# circuit0.net
KiCad netlist of a schematic drawn in EAGLE
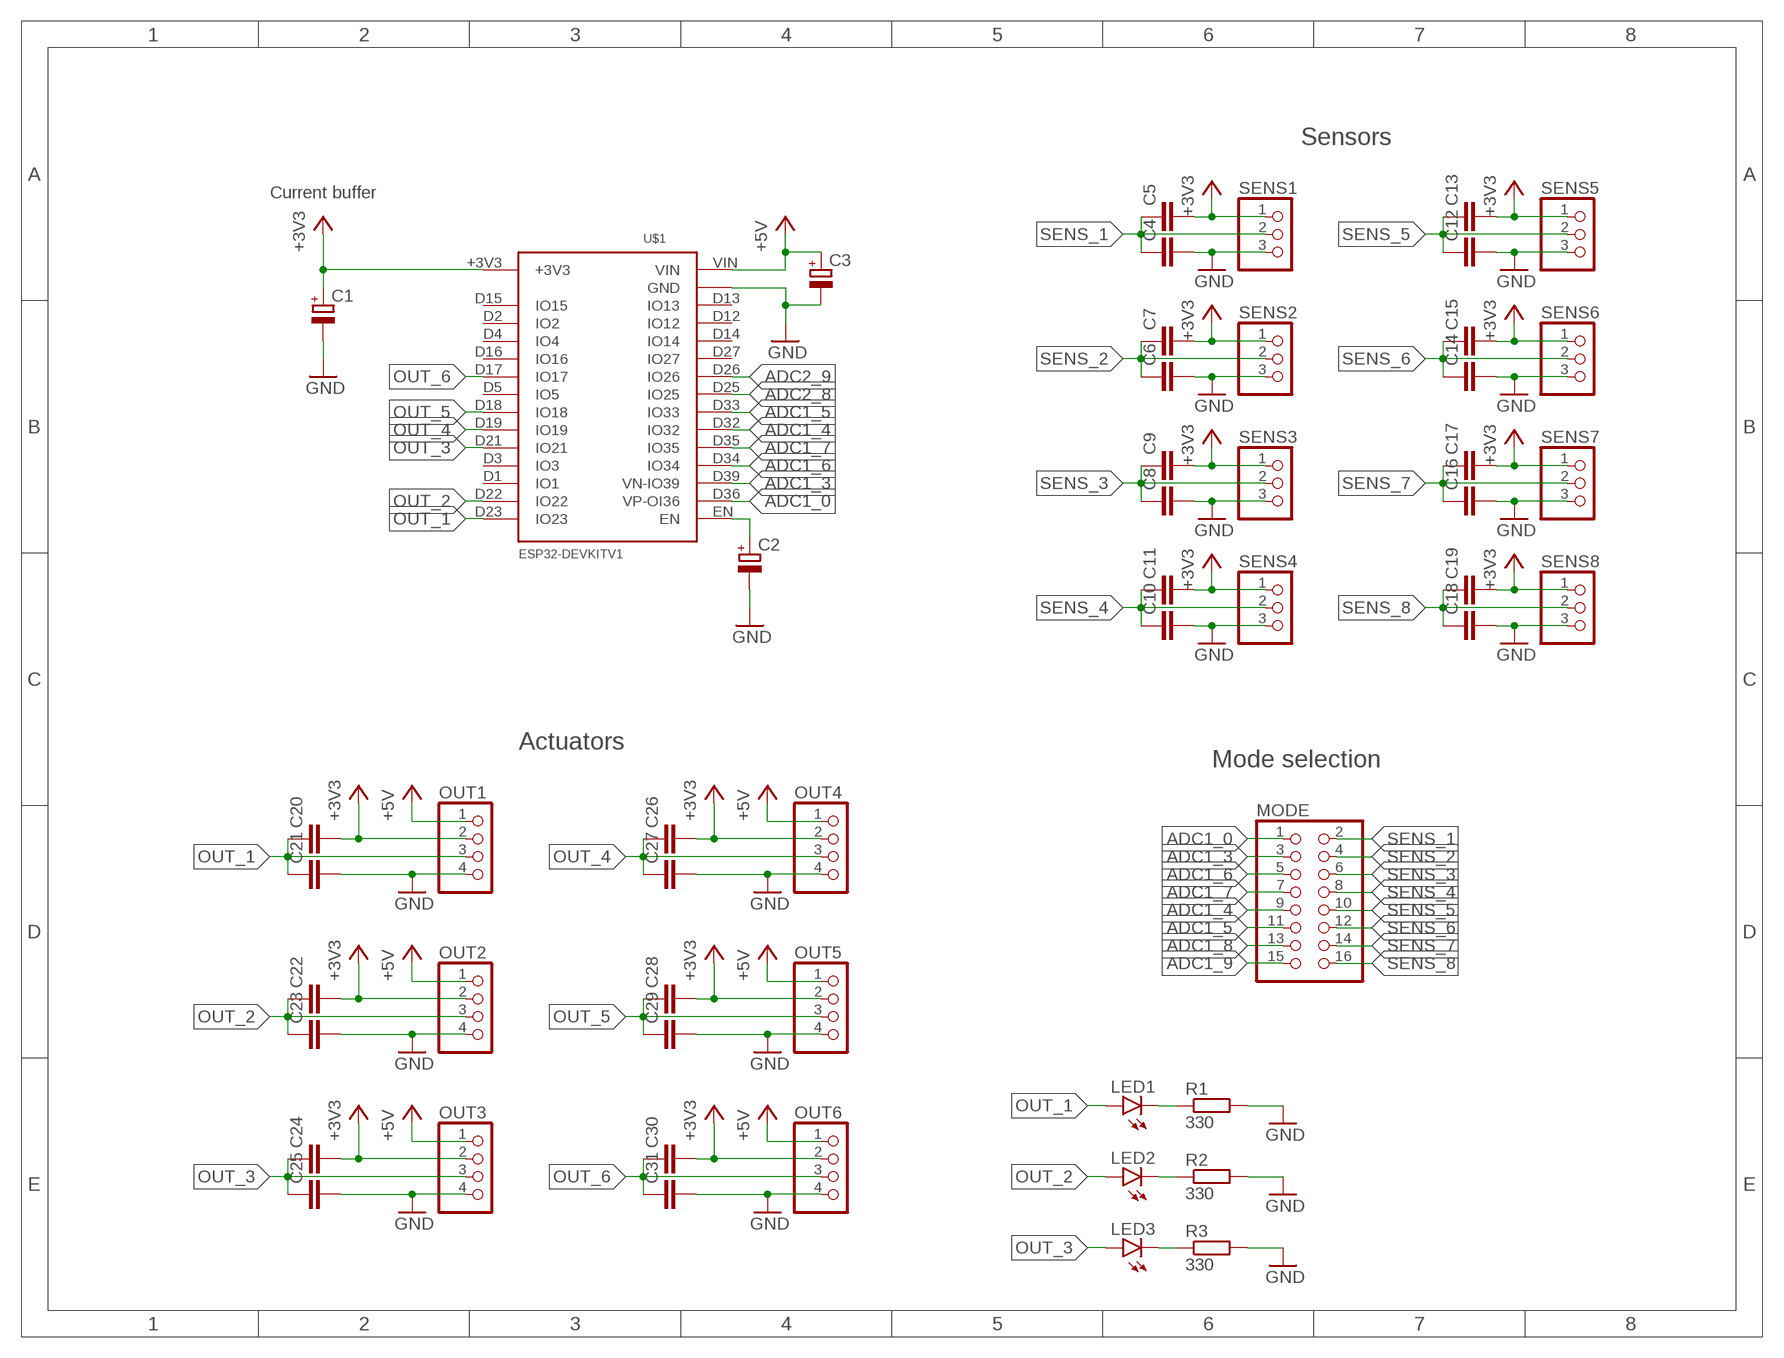
[diagram p0: schematic, sheet 1]

(export (version "E")
  (design (tool "Eeschema 10.0.6"))
  (components
    (comp (ref "C1")
      (value "CPOL-EUE3.5-8")
      (footprint "eagle-import:E3,5-8")
      (libsource (lib "eagle-import") (part "CPOL-EUE3.5-8"))
    )
    (comp (ref "C2")
      (value "CPOL-EUE3.5-8")
      (footprint "eagle-import:E3,5-8")
      (libsource (lib "eagle-import") (part "CPOL-EUE3.5-8"))
    )
    (comp (ref "C3")
      (value "CPOL-EUE3.5-8")
      (footprint "eagle-import:E3,5-8")
      (libsource (lib "eagle-import") (part "CPOL-EUE3.5-8"))
    )
    (comp (ref "C4")
      (value "C-EU025-030X050")
      (footprint "eagle-import:C025-030X050")
      (libsource (lib "eagle-import") (part "C-EU025-030X050"))
    )
    (comp (ref "C5")
      (value "C-EU025-030X050")
      (footprint "eagle-import:C025-030X050")
      (libsource (lib "eagle-import") (part "C-EU025-030X050"))
    )
    (comp (ref "C6")
      (value "C-EU025-030X050")
      (footprint "eagle-import:C025-030X050")
      (libsource (lib "eagle-import") (part "C-EU025-030X050"))
    )
    (comp (ref "C7")
      (value "C-EU025-030X050")
      (footprint "eagle-import:C025-030X050")
      (libsource (lib "eagle-import") (part "C-EU025-030X050"))
    )
    (comp (ref "C8")
      (value "C-EU025-030X050")
      (footprint "eagle-import:C025-030X050")
      (libsource (lib "eagle-import") (part "C-EU025-030X050"))
    )
    (comp (ref "C9")
      (value "C-EU025-030X050")
      (footprint "eagle-import:C025-030X050")
      (libsource (lib "eagle-import") (part "C-EU025-030X050"))
    )
    (comp (ref "C10")
      (value "C-EU025-030X050")
      (footprint "eagle-import:C025-030X050")
      (libsource (lib "eagle-import") (part "C-EU025-030X050"))
    )
    (comp (ref "C11")
      (value "C-EU025-030X050")
      (footprint "eagle-import:C025-030X050")
      (libsource (lib "eagle-import") (part "C-EU025-030X050"))
    )
    (comp (ref "C12")
      (value "C-EU025-030X050")
      (footprint "eagle-import:C025-030X050")
      (libsource (lib "eagle-import") (part "C-EU025-030X050"))
    )
    (comp (ref "C13")
      (value "C-EU025-030X050")
      (footprint "eagle-import:C025-030X050")
      (libsource (lib "eagle-import") (part "C-EU025-030X050"))
    )
    (comp (ref "C14")
      (value "C-EU025-030X050")
      (footprint "eagle-import:C025-030X050")
      (libsource (lib "eagle-import") (part "C-EU025-030X050"))
    )
    (comp (ref "C15")
      (value "C-EU025-030X050")
      (footprint "eagle-import:C025-030X050")
      (libsource (lib "eagle-import") (part "C-EU025-030X050"))
    )
    (comp (ref "C16")
      (value "C-EU025-030X050")
      (footprint "eagle-import:C025-030X050")
      (libsource (lib "eagle-import") (part "C-EU025-030X050"))
    )
    (comp (ref "C17")
      (value "C-EU025-030X050")
      (footprint "eagle-import:C025-030X050")
      (libsource (lib "eagle-import") (part "C-EU025-030X050"))
    )
    (comp (ref "C18")
      (value "C-EU025-030X050")
      (footprint "eagle-import:C025-030X050")
      (libsource (lib "eagle-import") (part "C-EU025-030X050"))
    )
    (comp (ref "C19")
      (value "C-EU025-030X050")
      (footprint "eagle-import:C025-030X050")
      (libsource (lib "eagle-import") (part "C-EU025-030X050"))
    )
    (comp (ref "C20")
      (value "C-EU025-030X050")
      (footprint "eagle-import:C025-030X050")
      (libsource (lib "eagle-import") (part "C-EU025-030X050"))
    )
    (comp (ref "C21")
      (value "C-EU025-030X050")
      (footprint "eagle-import:C025-030X050")
      (libsource (lib "eagle-import") (part "C-EU025-030X050"))
    )
    (comp (ref "C22")
      (value "C-EU025-030X050")
      (footprint "eagle-import:C025-030X050")
      (libsource (lib "eagle-import") (part "C-EU025-030X050"))
    )
    (comp (ref "C23")
      (value "C-EU025-030X050")
      (footprint "eagle-import:C025-030X050")
      (libsource (lib "eagle-import") (part "C-EU025-030X050"))
    )
    (comp (ref "C24")
      (value "C-EU025-030X050")
      (footprint "eagle-import:C025-030X050")
      (libsource (lib "eagle-import") (part "C-EU025-030X050"))
    )
    (comp (ref "C25")
      (value "C-EU025-030X050")
      (footprint "eagle-import:C025-030X050")
      (libsource (lib "eagle-import") (part "C-EU025-030X050"))
    )
    (comp (ref "C26")
      (value "C-EU025-030X050")
      (footprint "eagle-import:C025-030X050")
      (libsource (lib "eagle-import") (part "C-EU025-030X050"))
    )
    (comp (ref "C27")
      (value "C-EU025-030X050")
      (footprint "eagle-import:C025-030X050")
      (libsource (lib "eagle-import") (part "C-EU025-030X050"))
    )
    (comp (ref "C28")
      (value "C-EU025-030X050")
      (footprint "eagle-import:C025-030X050")
      (libsource (lib "eagle-import") (part "C-EU025-030X050"))
    )
    (comp (ref "C29")
      (value "C-EU025-030X050")
      (footprint "eagle-import:C025-030X050")
      (libsource (lib "eagle-import") (part "C-EU025-030X050"))
    )
    (comp (ref "C30")
      (value "C-EU025-030X050")
      (footprint "eagle-import:C025-030X050")
      (libsource (lib "eagle-import") (part "C-EU025-030X050"))
    )
    (comp (ref "C31")
      (value "C-EU025-030X050")
      (footprint "eagle-import:C025-030X050")
      (libsource (lib "eagle-import") (part "C-EU025-030X050"))
    )
    (comp (ref "LED1")
      (value "LED3MM")
      (footprint "eagle-import:LED3MM")
      (libsource (lib "eagle-import") (part "LED3MM"))
    )
    (comp (ref "LED2")
      (value "LED3MM")
      (footprint "eagle-import:LED3MM")
      (libsource (lib "eagle-import") (part "LED3MM"))
    )
    (comp (ref "LED3")
      (value "LED3MM")
      (footprint "eagle-import:LED3MM")
      (libsource (lib "eagle-import") (part "LED3MM"))
    )
    (comp (ref "MODE")
      (value "PINHD-2X8")
      (footprint "eagle-import:2X08")
      (libsource (lib "eagle-import") (part "PINHD-2X8"))
    )
    (comp (ref "OUT1")
      (value "PINHD-1X4")
      (footprint "eagle-import:1X04")
      (libsource (lib "eagle-import") (part "PINHD-1X4"))
    )
    (comp (ref "OUT2")
      (value "PINHD-1X4")
      (footprint "eagle-import:1X04")
      (libsource (lib "eagle-import") (part "PINHD-1X4"))
    )
    (comp (ref "OUT3")
      (value "PINHD-1X4")
      (footprint "eagle-import:1X04")
      (libsource (lib "eagle-import") (part "PINHD-1X4"))
    )
    (comp (ref "OUT4")
      (value "PINHD-1X4")
      (footprint "eagle-import:1X04")
      (libsource (lib "eagle-import") (part "PINHD-1X4"))
    )
    (comp (ref "OUT5")
      (value "PINHD-1X4")
      (footprint "eagle-import:1X04")
      (libsource (lib "eagle-import") (part "PINHD-1X4"))
    )
    (comp (ref "OUT6")
      (value "PINHD-1X4")
      (footprint "eagle-import:1X04")
      (libsource (lib "eagle-import") (part "PINHD-1X4"))
    )
    (comp (ref "R1")
      (value "330")
      (footprint "eagle-import:0204_7")
      (libsource (lib "eagle-import") (part "R-EU_0204/7"))
    )
    (comp (ref "R2")
      (value "330")
      (footprint "eagle-import:0204_7")
      (libsource (lib "eagle-import") (part "R-EU_0204/7"))
    )
    (comp (ref "R3")
      (value "330")
      (footprint "eagle-import:0204_7")
      (libsource (lib "eagle-import") (part "R-EU_0204/7"))
    )
    (comp (ref "SENS1")
      (value "PINHD-1X3")
      (footprint "eagle-import:1X03")
      (libsource (lib "eagle-import") (part "PINHD-1X3"))
    )
    (comp (ref "SENS2")
      (value "PINHD-1X3")
      (footprint "eagle-import:1X03")
      (libsource (lib "eagle-import") (part "PINHD-1X3"))
    )
    (comp (ref "SENS3")
      (value "PINHD-1X3")
      (footprint "eagle-import:1X03")
      (libsource (lib "eagle-import") (part "PINHD-1X3"))
    )
    (comp (ref "SENS4")
      (value "PINHD-1X3")
      (footprint "eagle-import:1X03")
      (libsource (lib "eagle-import") (part "PINHD-1X3"))
    )
    (comp (ref "SENS5")
      (value "PINHD-1X3")
      (footprint "eagle-import:1X03")
      (libsource (lib "eagle-import") (part "PINHD-1X3"))
    )
    (comp (ref "SENS6")
      (value "PINHD-1X3")
      (footprint "eagle-import:1X03")
      (libsource (lib "eagle-import") (part "PINHD-1X3"))
    )
    (comp (ref "SENS7")
      (value "PINHD-1X3")
      (footprint "eagle-import:1X03")
      (libsource (lib "eagle-import") (part "PINHD-1X3"))
    )
    (comp (ref "SENS8")
      (value "PINHD-1X3")
      (footprint "eagle-import:1X03")
      (libsource (lib "eagle-import") (part "PINHD-1X3"))
    )
    (comp (ref "U$1")
      (value "ESP32DEVKITV1")
      (footprint "eagle-import:ESP32-DEVKITV1")
      (libsource (lib "eagle-import") (part "ESP32DEVKITV1"))
    )
  )
  (nets
    (net (code "1") (name "+3V3") (class "Default")
      (node (ref "C1") (pin "+") (pinfunction "+_+") (pintype "passive"))
      (node (ref "C11") (pin "2") (pinfunction "2_2") (pintype "passive"))
      (node (ref "C13") (pin "2") (pinfunction "2_2") (pintype "passive"))
      (node (ref "C15") (pin "2") (pinfunction "2_2") (pintype "passive"))
      (node (ref "C17") (pin "2") (pinfunction "2_2") (pintype "passive"))
      (node (ref "C19") (pin "2") (pinfunction "2_2") (pintype "passive"))
      (node (ref "C20") (pin "2") (pinfunction "2_2") (pintype "passive"))
      (node (ref "C22") (pin "2") (pinfunction "2_2") (pintype "passive"))
      (node (ref "C24") (pin "2") (pinfunction "2_2") (pintype "passive"))
      (node (ref "C26") (pin "2") (pinfunction "2_2") (pintype "passive"))
      (node (ref "C28") (pin "2") (pinfunction "2_2") (pintype "passive"))
      (node (ref "C30") (pin "2") (pinfunction "2_2") (pintype "passive"))
      (node (ref "C5") (pin "2") (pinfunction "2_2") (pintype "passive"))
      (node (ref "C7") (pin "2") (pinfunction "2_2") (pintype "passive"))
      (node (ref "C9") (pin "2") (pinfunction "2_2") (pintype "passive"))
      (node (ref "OUT1") (pin "2") (pinfunction "2_2") (pintype "passive"))
      (node (ref "OUT2") (pin "2") (pinfunction "2_2") (pintype "passive"))
      (node (ref "OUT3") (pin "2") (pinfunction "2_2") (pintype "passive"))
      (node (ref "OUT4") (pin "2") (pinfunction "2_2") (pintype "passive"))
      (node (ref "OUT5") (pin "2") (pinfunction "2_2") (pintype "passive"))
      (node (ref "OUT6") (pin "2") (pinfunction "2_2") (pintype "passive"))
      (node (ref "SENS1") (pin "1") (pinfunction "1_1") (pintype "passive"))
      (node (ref "SENS2") (pin "1") (pinfunction "1_1") (pintype "passive"))
      (node (ref "SENS3") (pin "1") (pinfunction "1_1") (pintype "passive"))
      (node (ref "SENS4") (pin "1") (pinfunction "1_1") (pintype "passive"))
      (node (ref "SENS5") (pin "1") (pinfunction "1_1") (pintype "passive"))
      (node (ref "SENS6") (pin "1") (pinfunction "1_1") (pintype "passive"))
      (node (ref "SENS7") (pin "1") (pinfunction "1_1") (pintype "passive"))
      (node (ref "SENS8") (pin "1") (pinfunction "1_1") (pintype "passive"))
      (node (ref "U$1") (pin "+3V3") (pinfunction "+3V3_+3V3") (pintype "power_in"))
    )
    (net (code "2") (name "+5V") (class "Default")
      (node (ref "C3") (pin "+") (pinfunction "+_+") (pintype "passive"))
      (node (ref "OUT1") (pin "1") (pinfunction "1_1") (pintype "passive"))
      (node (ref "OUT2") (pin "1") (pinfunction "1_1") (pintype "passive"))
      (node (ref "OUT3") (pin "1") (pinfunction "1_1") (pintype "passive"))
      (node (ref "OUT4") (pin "1") (pinfunction "1_1") (pintype "passive"))
      (node (ref "OUT5") (pin "1") (pinfunction "1_1") (pintype "passive"))
      (node (ref "OUT6") (pin "1") (pinfunction "1_1") (pintype "passive"))
      (node (ref "U$1") (pin "VIN") (pinfunction "VIN_VIN") (pintype "power_in"))
    )
    (net (code "3") (name "ADC1_0") (class "Default")
      (node (ref "MODE") (pin "1") (pinfunction "1_1") (pintype "passive"))
      (node (ref "U$1") (pin "D36") (pinfunction "VP-OI36_D36") (pintype "bidirectional"))
    )
    (net (code "4") (name "ADC1_3") (class "Default")
      (node (ref "MODE") (pin "3") (pinfunction "3_3") (pintype "passive"))
      (node (ref "U$1") (pin "D39") (pinfunction "VN-IO39_D39") (pintype "bidirectional"))
    )
    (net (code "5") (name "ADC1_4") (class "Default")
      (node (ref "MODE") (pin "9") (pinfunction "9_9") (pintype "passive"))
      (node (ref "U$1") (pin "D32") (pinfunction "IO32_D32") (pintype "bidirectional"))
    )
    (net (code "6") (name "ADC1_5") (class "Default")
      (node (ref "MODE") (pin "11") (pinfunction "11_11") (pintype "passive"))
      (node (ref "U$1") (pin "D33") (pinfunction "IO33_D33") (pintype "bidirectional"))
    )
    (net (code "7") (name "ADC1_6") (class "Default")
      (node (ref "MODE") (pin "5") (pinfunction "5_5") (pintype "passive"))
      (node (ref "U$1") (pin "D34") (pinfunction "IO34_D34") (pintype "bidirectional"))
    )
    (net (code "8") (name "ADC1_7") (class "Default")
      (node (ref "MODE") (pin "7") (pinfunction "7_7") (pintype "passive"))
      (node (ref "U$1") (pin "D35") (pinfunction "IO35_D35") (pintype "bidirectional"))
    )
    (net (code "9") (name "ADC1_8") (class "Default")
      (node (ref "MODE") (pin "13") (pinfunction "13_13") (pintype "passive"))
    )
    (net (code "10") (name "ADC1_9") (class "Default")
      (node (ref "MODE") (pin "15") (pinfunction "15_15") (pintype "passive"))
    )
    (net (code "11") (name "ADC2_8") (class "Default")
      (node (ref "U$1") (pin "D25") (pinfunction "IO25_D25") (pintype "bidirectional"))
    )
    (net (code "12") (name "ADC2_9") (class "Default")
      (node (ref "U$1") (pin "D26") (pinfunction "IO26_D26") (pintype "bidirectional"))
    )
    (net (code "13") (name "GND") (class "Default")
      (node (ref "C1") (pin "-") (pinfunction "-_-") (pintype "passive"))
      (node (ref "C10") (pin "2") (pinfunction "2_2") (pintype "passive"))
      (node (ref "C12") (pin "2") (pinfunction "2_2") (pintype "passive"))
      (node (ref "C14") (pin "2") (pinfunction "2_2") (pintype "passive"))
      (node (ref "C16") (pin "2") (pinfunction "2_2") (pintype "passive"))
      (node (ref "C18") (pin "2") (pinfunction "2_2") (pintype "passive"))
      (node (ref "C2") (pin "-") (pinfunction "-_-") (pintype "passive"))
      (node (ref "C21") (pin "2") (pinfunction "2_2") (pintype "passive"))
      (node (ref "C23") (pin "2") (pinfunction "2_2") (pintype "passive"))
      (node (ref "C25") (pin "2") (pinfunction "2_2") (pintype "passive"))
      (node (ref "C27") (pin "2") (pinfunction "2_2") (pintype "passive"))
      (node (ref "C29") (pin "2") (pinfunction "2_2") (pintype "passive"))
      (node (ref "C3") (pin "-") (pinfunction "-_-") (pintype "passive"))
      (node (ref "C31") (pin "2") (pinfunction "2_2") (pintype "passive"))
      (node (ref "C4") (pin "2") (pinfunction "2_2") (pintype "passive"))
      (node (ref "C6") (pin "2") (pinfunction "2_2") (pintype "passive"))
      (node (ref "C8") (pin "2") (pinfunction "2_2") (pintype "passive"))
      (node (ref "OUT1") (pin "4") (pinfunction "4_4") (pintype "passive"))
      (node (ref "OUT2") (pin "4") (pinfunction "4_4") (pintype "passive"))
      (node (ref "OUT3") (pin "4") (pinfunction "4_4") (pintype "passive"))
      (node (ref "OUT4") (pin "4") (pinfunction "4_4") (pintype "passive"))
      (node (ref "OUT5") (pin "4") (pinfunction "4_4") (pintype "passive"))
      (node (ref "OUT6") (pin "4") (pinfunction "4_4") (pintype "passive"))
      (node (ref "R1") (pin "2") (pinfunction "2_2") (pintype "passive"))
      (node (ref "R2") (pin "2") (pinfunction "2_2") (pintype "passive"))
      (node (ref "R3") (pin "2") (pinfunction "2_2") (pintype "passive"))
      (node (ref "SENS1") (pin "3") (pinfunction "3_3") (pintype "passive"))
      (node (ref "SENS2") (pin "3") (pinfunction "3_3") (pintype "passive"))
      (node (ref "SENS3") (pin "3") (pinfunction "3_3") (pintype "passive"))
      (node (ref "SENS4") (pin "3") (pinfunction "3_3") (pintype "passive"))
      (node (ref "SENS5") (pin "3") (pinfunction "3_3") (pintype "passive"))
      (node (ref "SENS6") (pin "3") (pinfunction "3_3") (pintype "passive"))
      (node (ref "SENS7") (pin "3") (pinfunction "3_3") (pintype "passive"))
      (node (ref "SENS8") (pin "3") (pinfunction "3_3") (pintype "passive"))
      (node (ref "U$1") (pin "GND") (pinfunction "GND_GND") (pintype "output"))
      (node (ref "U$1") (pin "GND@2") (pinfunction "GND_GND@2") (pintype "output"))
    )
    (net (code "14") (name "Net-(C2-Pad+)") (class "Default")
      (node (ref "C2") (pin "+") (pinfunction "+_+") (pintype "passive"))
      (node (ref "U$1") (pin "EN") (pinfunction "EN_EN") (pintype "bidirectional"))
    )
    (net (code "15") (name "Net-(LED1-C)") (class "Default")
      (node (ref "LED1") (pin "K") (pinfunction "C_K") (pintype "passive"))
      (node (ref "R1") (pin "1") (pinfunction "1_1") (pintype "passive"))
    )
    (net (code "16") (name "Net-(LED2-C)") (class "Default")
      (node (ref "LED2") (pin "K") (pinfunction "C_K") (pintype "passive"))
      (node (ref "R2") (pin "1") (pinfunction "1_1") (pintype "passive"))
    )
    (net (code "17") (name "Net-(LED3-C)") (class "Default")
      (node (ref "LED3") (pin "K") (pinfunction "C_K") (pintype "passive"))
      (node (ref "R3") (pin "1") (pinfunction "1_1") (pintype "passive"))
    )
    (net (code "18") (name "OUT_1") (class "Default")
      (node (ref "C20") (pin "1") (pinfunction "1_1") (pintype "passive"))
      (node (ref "C21") (pin "1") (pinfunction "1_1") (pintype "passive"))
      (node (ref "LED1") (pin "A") (pinfunction "A_A") (pintype "passive"))
      (node (ref "OUT1") (pin "3") (pinfunction "3_3") (pintype "passive"))
      (node (ref "U$1") (pin "D23") (pinfunction "IO23_D23") (pintype "bidirectional"))
    )
    (net (code "19") (name "OUT_2") (class "Default")
      (node (ref "C22") (pin "1") (pinfunction "1_1") (pintype "passive"))
      (node (ref "C23") (pin "1") (pinfunction "1_1") (pintype "passive"))
      (node (ref "LED2") (pin "A") (pinfunction "A_A") (pintype "passive"))
      (node (ref "OUT2") (pin "3") (pinfunction "3_3") (pintype "passive"))
      (node (ref "U$1") (pin "D22") (pinfunction "IO22_D22") (pintype "bidirectional"))
    )
    (net (code "20") (name "OUT_3") (class "Default")
      (node (ref "C24") (pin "1") (pinfunction "1_1") (pintype "passive"))
      (node (ref "C25") (pin "1") (pinfunction "1_1") (pintype "passive"))
      (node (ref "LED3") (pin "A") (pinfunction "A_A") (pintype "passive"))
      (node (ref "OUT3") (pin "3") (pinfunction "3_3") (pintype "passive"))
      (node (ref "U$1") (pin "D21") (pinfunction "IO21_D21") (pintype "bidirectional"))
    )
    (net (code "21") (name "OUT_4") (class "Default")
      (node (ref "C26") (pin "1") (pinfunction "1_1") (pintype "passive"))
      (node (ref "C27") (pin "1") (pinfunction "1_1") (pintype "passive"))
      (node (ref "OUT4") (pin "3") (pinfunction "3_3") (pintype "passive"))
      (node (ref "U$1") (pin "D19") (pinfunction "IO19_D19") (pintype "bidirectional"))
    )
    (net (code "22") (name "OUT_5") (class "Default")
      (node (ref "C28") (pin "1") (pinfunction "1_1") (pintype "passive"))
      (node (ref "C29") (pin "1") (pinfunction "1_1") (pintype "passive"))
      (node (ref "OUT5") (pin "3") (pinfunction "3_3") (pintype "passive"))
      (node (ref "U$1") (pin "D18") (pinfunction "IO18_D18") (pintype "bidirectional"))
    )
    (net (code "23") (name "OUT_6") (class "Default")
      (node (ref "C30") (pin "1") (pinfunction "1_1") (pintype "passive"))
      (node (ref "C31") (pin "1") (pinfunction "1_1") (pintype "passive"))
      (node (ref "OUT6") (pin "3") (pinfunction "3_3") (pintype "passive"))
      (node (ref "U$1") (pin "D17") (pinfunction "IO17_D17") (pintype "bidirectional"))
    )
    (net (code "24") (name "SENS_1") (class "Default")
      (node (ref "C4") (pin "1") (pinfunction "1_1") (pintype "passive"))
      (node (ref "C5") (pin "1") (pinfunction "1_1") (pintype "passive"))
      (node (ref "MODE") (pin "2") (pinfunction "2_2") (pintype "passive"))
      (node (ref "SENS1") (pin "2") (pinfunction "2_2") (pintype "passive"))
    )
    (net (code "25") (name "SENS_2") (class "Default")
      (node (ref "C6") (pin "1") (pinfunction "1_1") (pintype "passive"))
      (node (ref "C7") (pin "1") (pinfunction "1_1") (pintype "passive"))
      (node (ref "MODE") (pin "4") (pinfunction "4_4") (pintype "passive"))
      (node (ref "SENS2") (pin "2") (pinfunction "2_2") (pintype "passive"))
    )
    (net (code "26") (name "SENS_3") (class "Default")
      (node (ref "C8") (pin "1") (pinfunction "1_1") (pintype "passive"))
      (node (ref "C9") (pin "1") (pinfunction "1_1") (pintype "passive"))
      (node (ref "MODE") (pin "6") (pinfunction "6_6") (pintype "passive"))
      (node (ref "SENS3") (pin "2") (pinfunction "2_2") (pintype "passive"))
    )
    (net (code "27") (name "SENS_4") (class "Default")
      (node (ref "C10") (pin "1") (pinfunction "1_1") (pintype "passive"))
      (node (ref "C11") (pin "1") (pinfunction "1_1") (pintype "passive"))
      (node (ref "MODE") (pin "8") (pinfunction "8_8") (pintype "passive"))
      (node (ref "SENS4") (pin "2") (pinfunction "2_2") (pintype "passive"))
    )
    (net (code "28") (name "SENS_5") (class "Default")
      (node (ref "C12") (pin "1") (pinfunction "1_1") (pintype "passive"))
      (node (ref "C13") (pin "1") (pinfunction "1_1") (pintype "passive"))
      (node (ref "MODE") (pin "10") (pinfunction "10_10") (pintype "passive"))
      (node (ref "SENS5") (pin "2") (pinfunction "2_2") (pintype "passive"))
    )
    (net (code "29") (name "SENS_6") (class "Default")
      (node (ref "C14") (pin "1") (pinfunction "1_1") (pintype "passive"))
      (node (ref "C15") (pin "1") (pinfunction "1_1") (pintype "passive"))
      (node (ref "MODE") (pin "12") (pinfunction "12_12") (pintype "passive"))
      (node (ref "SENS6") (pin "2") (pinfunction "2_2") (pintype "passive"))
    )
    (net (code "30") (name "SENS_7") (class "Default")
      (node (ref "C16") (pin "1") (pinfunction "1_1") (pintype "passive"))
      (node (ref "C17") (pin "1") (pinfunction "1_1") (pintype "passive"))
      (node (ref "MODE") (pin "14") (pinfunction "14_14") (pintype "passive"))
      (node (ref "SENS7") (pin "2") (pinfunction "2_2") (pintype "passive"))
    )
    (net (code "31") (name "SENS_8") (class "Default")
      (node (ref "C18") (pin "1") (pinfunction "1_1") (pintype "passive"))
      (node (ref "C19") (pin "1") (pinfunction "1_1") (pintype "passive"))
      (node (ref "MODE") (pin "16") (pinfunction "16_16") (pintype "passive"))
      (node (ref "SENS8") (pin "2") (pinfunction "2_2") (pintype "passive"))
    )
    (net (code "32") (name "unconnected-(U$1-IO1-PadD1)") (class "Default")
      (node (ref "U$1") (pin "D1") (pinfunction "IO1_D1") (pintype "bidirectional"))
    )
    (net (code "33") (name "unconnected-(U$1-IO2-PadD2)") (class "Default")
      (node (ref "U$1") (pin "D2") (pinfunction "IO2_D2") (pintype "bidirectional"))
    )
    (net (code "34") (name "unconnected-(U$1-IO3-PadD3)") (class "Default")
      (node (ref "U$1") (pin "D3") (pinfunction "IO3_D3") (pintype "bidirectional"))
    )
    (net (code "35") (name "unconnected-(U$1-IO4-PadD4)") (class "Default")
      (node (ref "U$1") (pin "D4") (pinfunction "IO4_D4") (pintype "bidirectional"))
    )
    (net (code "36") (name "unconnected-(U$1-IO5-PadD5)") (class "Default")
      (node (ref "U$1") (pin "D5") (pinfunction "IO5_D5") (pintype "bidirectional"))
    )
    (net (code "37") (name "unconnected-(U$1-IO12-PadD12)") (class "Default")
      (node (ref "U$1") (pin "D12") (pinfunction "IO12_D12") (pintype "bidirectional"))
    )
    (net (code "38") (name "unconnected-(U$1-IO13-PadD13)") (class "Default")
      (node (ref "U$1") (pin "D13") (pinfunction "IO13_D13") (pintype "bidirectional"))
    )
    (net (code "39") (name "unconnected-(U$1-IO14-PadD14)") (class "Default")
      (node (ref "U$1") (pin "D14") (pinfunction "IO14_D14") (pintype "bidirectional"))
    )
    (net (code "40") (name "unconnected-(U$1-IO15-PadD15)") (class "Default")
      (node (ref "U$1") (pin "D15") (pinfunction "IO15_D15") (pintype "bidirectional"))
    )
    (net (code "41") (name "unconnected-(U$1-IO16-PadD16)") (class "Default")
      (node (ref "U$1") (pin "D16") (pinfunction "IO16_D16") (pintype "bidirectional"))
    )
    (net (code "42") (name "unconnected-(U$1-IO27-PadD27)") (class "Default")
      (node (ref "U$1") (pin "D27") (pinfunction "IO27_D27") (pintype "bidirectional"))
    )
  )
)
